# jstBloomsch.net
KiCad netlist of a schematic drawn in EAGLE
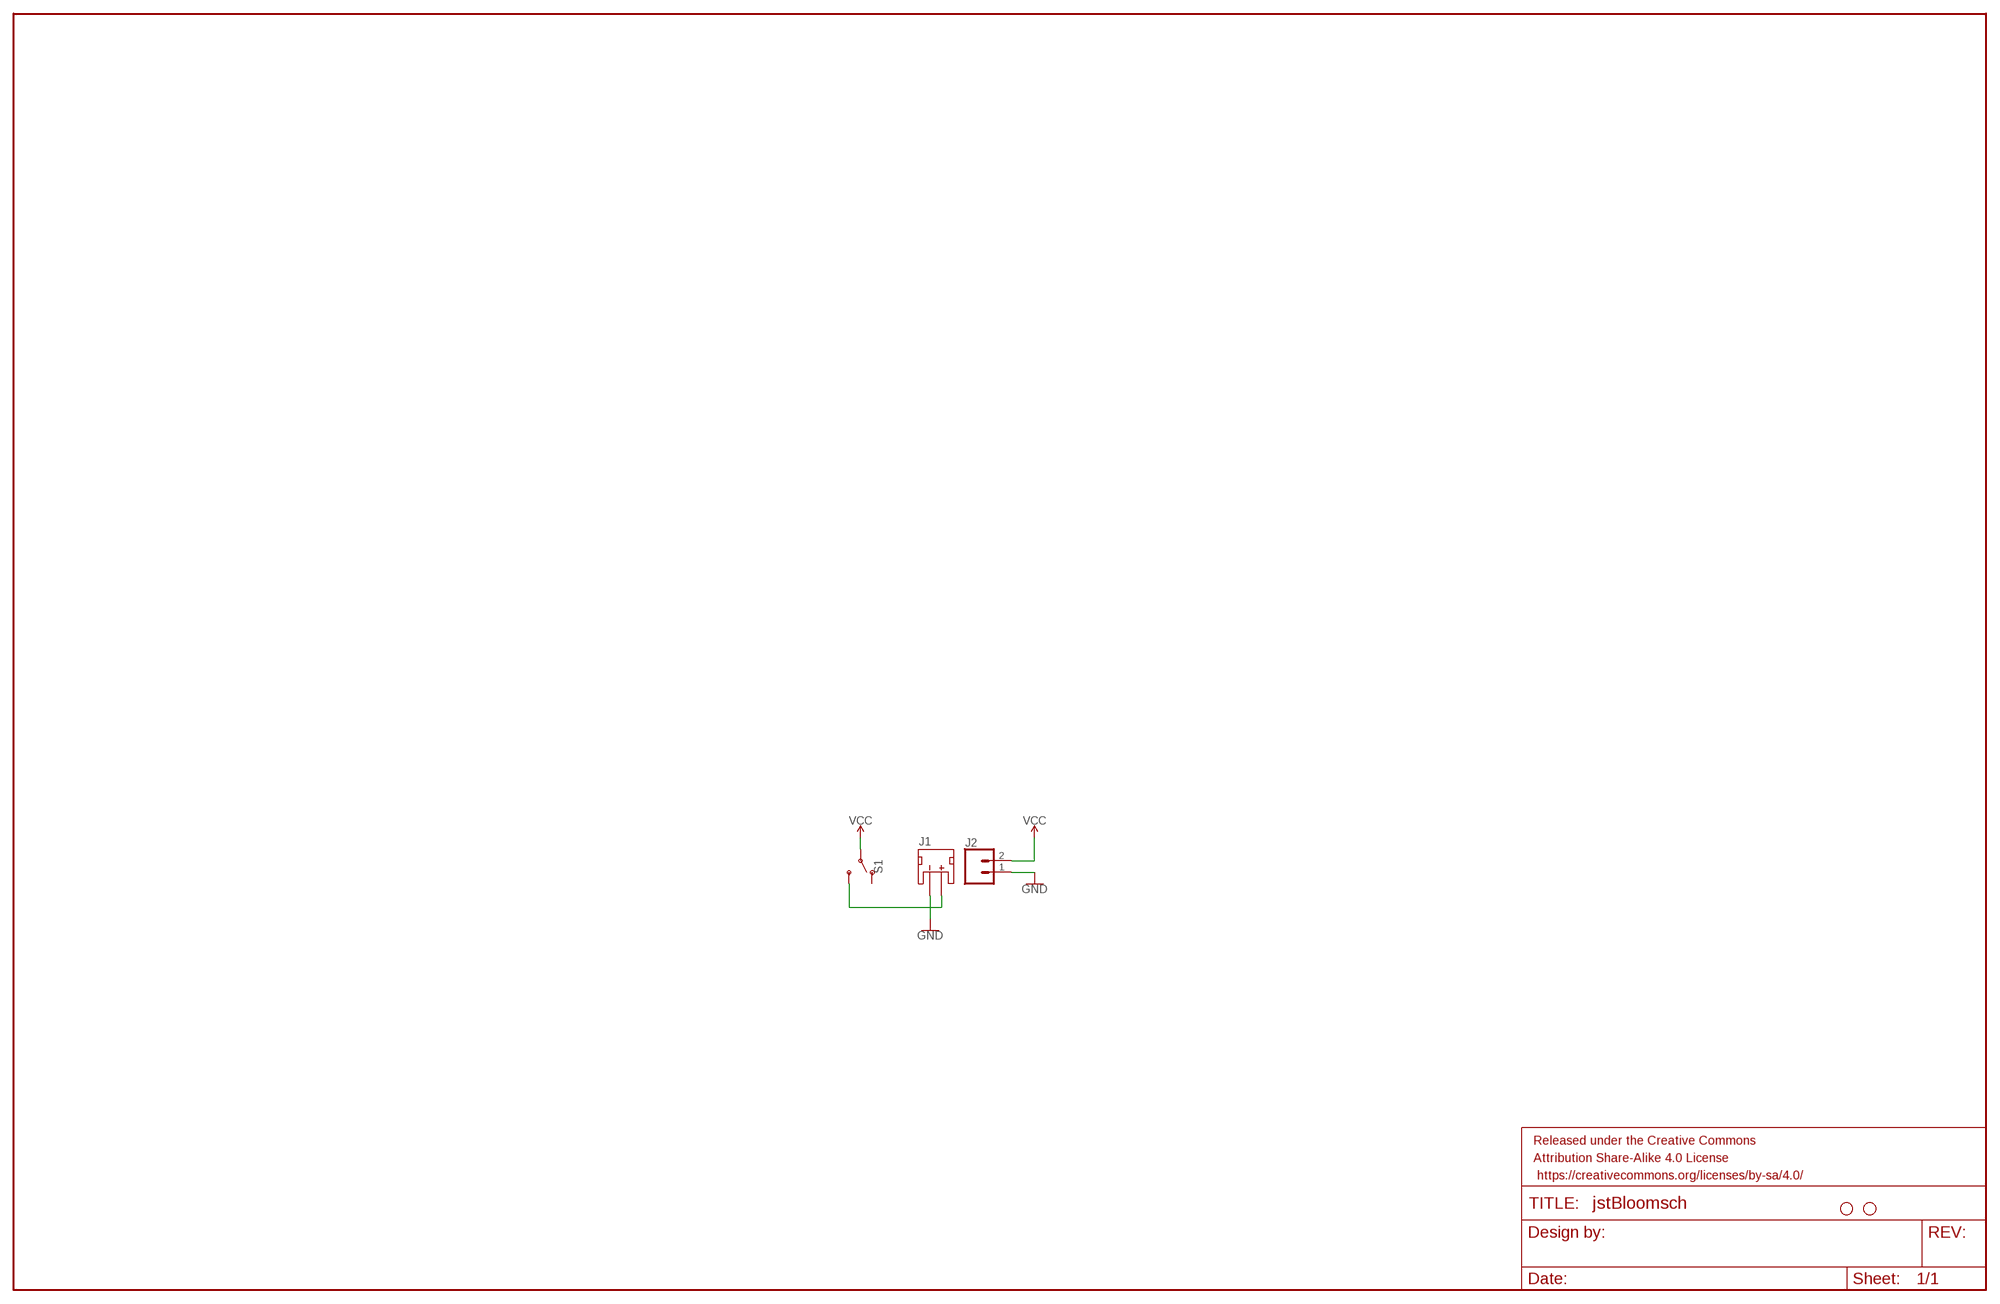
[diagram p0: schematic, sheet 1]

(export (version "E")
  (design (tool "Eeschema 10.0.6"))
  (components
    (comp (ref "FRAME1")
      (value "FRAME-LEDGER")
      (footprint "eagle-import:CREATIVE_COMMONS")
      (libsource (lib "eagle-import") (part "FRAME-LEDGER"))
    )
    (comp (ref "H1")
      (value "STAND-OFFTIGHT")
      (footprint "eagle-import:STAND-OFF-TIGHT")
      (libsource (lib "eagle-import") (part "STAND-OFFTIGHT"))
    )
    (comp (ref "H2")
      (value "STAND-OFFTIGHT")
      (footprint "eagle-import:STAND-OFF-TIGHT")
      (libsource (lib "eagle-import") (part "STAND-OFFTIGHT"))
    )
    (comp (ref "J1")
      (value "JST_2MM_MALE")
      (footprint "eagle-import:JST-2-SMD")
      (libsource (lib "eagle-import") (part "JST_2MM_MALE"))
    )
    (comp (ref "J2")
      (value "CONN_021X02_NO_SILK")
      (footprint "eagle-import:1X02_NO_SILK")
      (libsource (lib "eagle-import") (part "CONN_021X02_NO_SILK"))
    )
    (comp (ref "S1")
      (value "SWITCH-SPDT-SMD-RIGHT-ANGLE")
      (footprint "eagle-import:SWITCH_SPST_SMD_A")
      (libsource (lib "eagle-import") (part "SWITCH-SPDT-SMD-RIGHT-ANGLE"))
    )
  )
  (nets
    (net (code "1") (name "GND") (class "Default")
      (node (ref "J1") (pin "1") (pinfunction "-_1") (pintype "bidirectional"))
      (node (ref "J2") (pin "1") (pinfunction "1_1") (pintype "passive"))
    )
    (net (code "2") (name "Net-(J1-+)") (class "Default")
      (node (ref "J1") (pin "2") (pinfunction "+_2") (pintype "bidirectional"))
      (node (ref "S1") (pin "3") (pinfunction "S_3") (pintype "passive"))
    )
    (net (code "3") (name "VCC") (class "Default")
      (node (ref "J2") (pin "2") (pinfunction "2_2") (pintype "passive"))
      (node (ref "S1") (pin "2") (pinfunction "P_2") (pintype "passive"))
    )
    (net (code "4") (name "unconnected-(J1-PAD1-PadNC1)") (class "Default")
      (node (ref "J1") (pin "NC1") (pinfunction "PAD1_NC1") (pintype "bidirectional"))
    )
    (net (code "5") (name "unconnected-(J1-PAD2-PadNC2)") (class "Default")
      (node (ref "J1") (pin "NC2") (pinfunction "PAD2_NC2") (pintype "bidirectional"))
    )
    (net (code "6") (name "unconnected-(S1-O-Pad1)") (class "Default")
      (node (ref "S1") (pin "1") (pinfunction "O_1") (pintype "passive"))
    )
  )
)
